# 4_SD_Card_NFC.net
KiCad netlist of a schematic drawn in Altium Designer
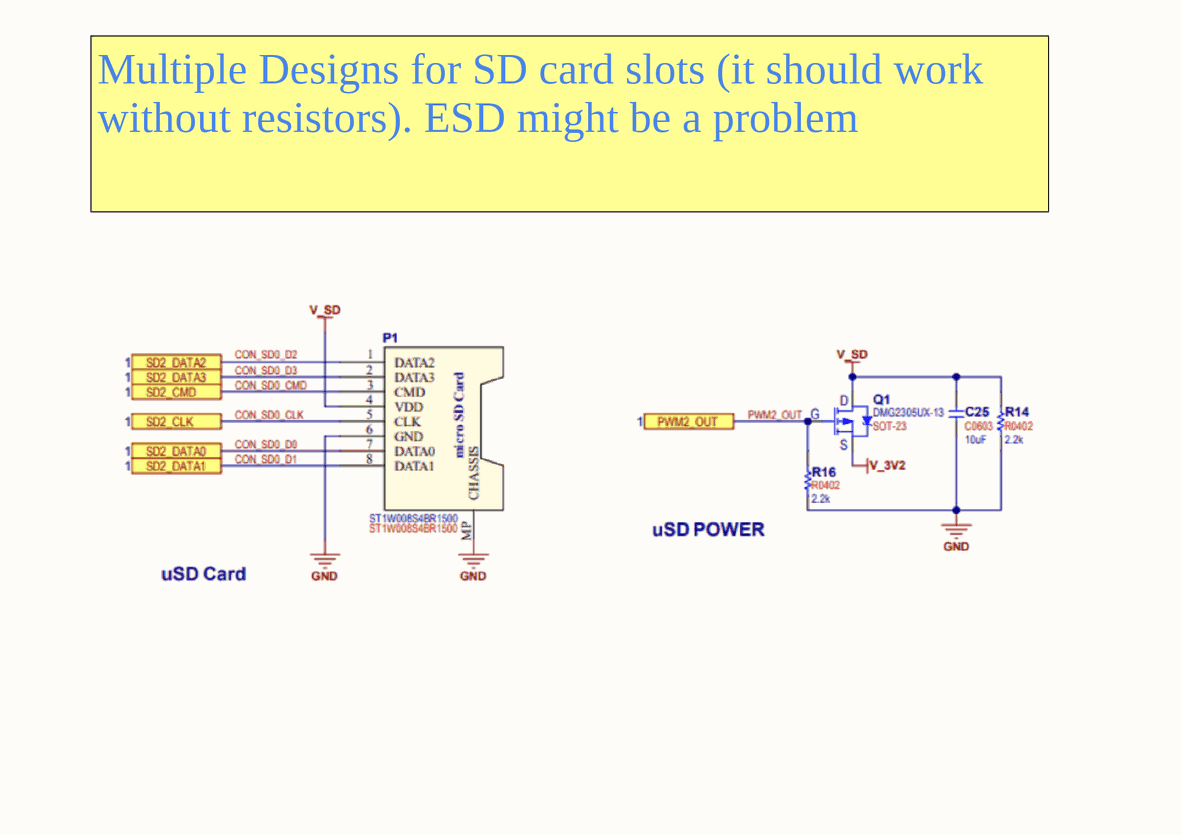
[diagram p0: 4_SD_Card_NFC.SchDoc, top middle]
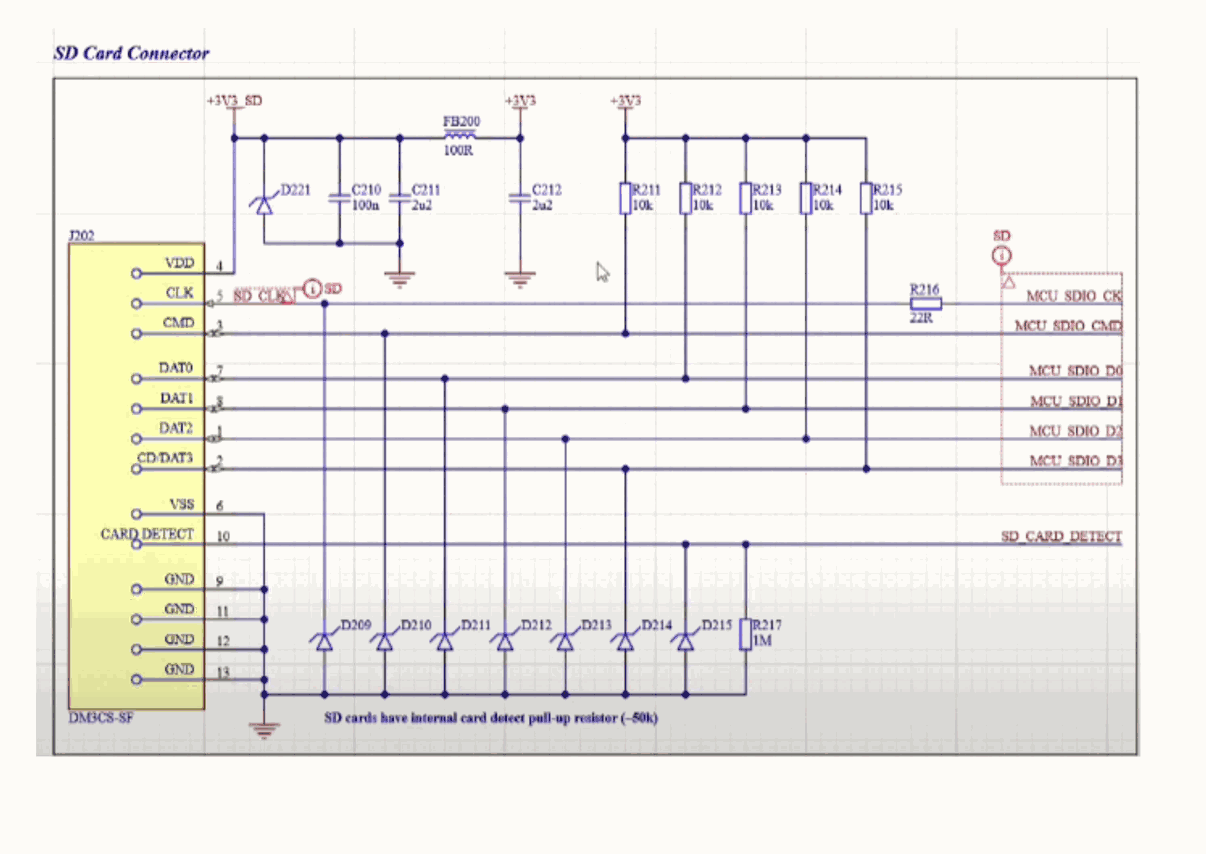
[diagram p1: 4_SD_Card_NFC.SchDoc, bottom left]
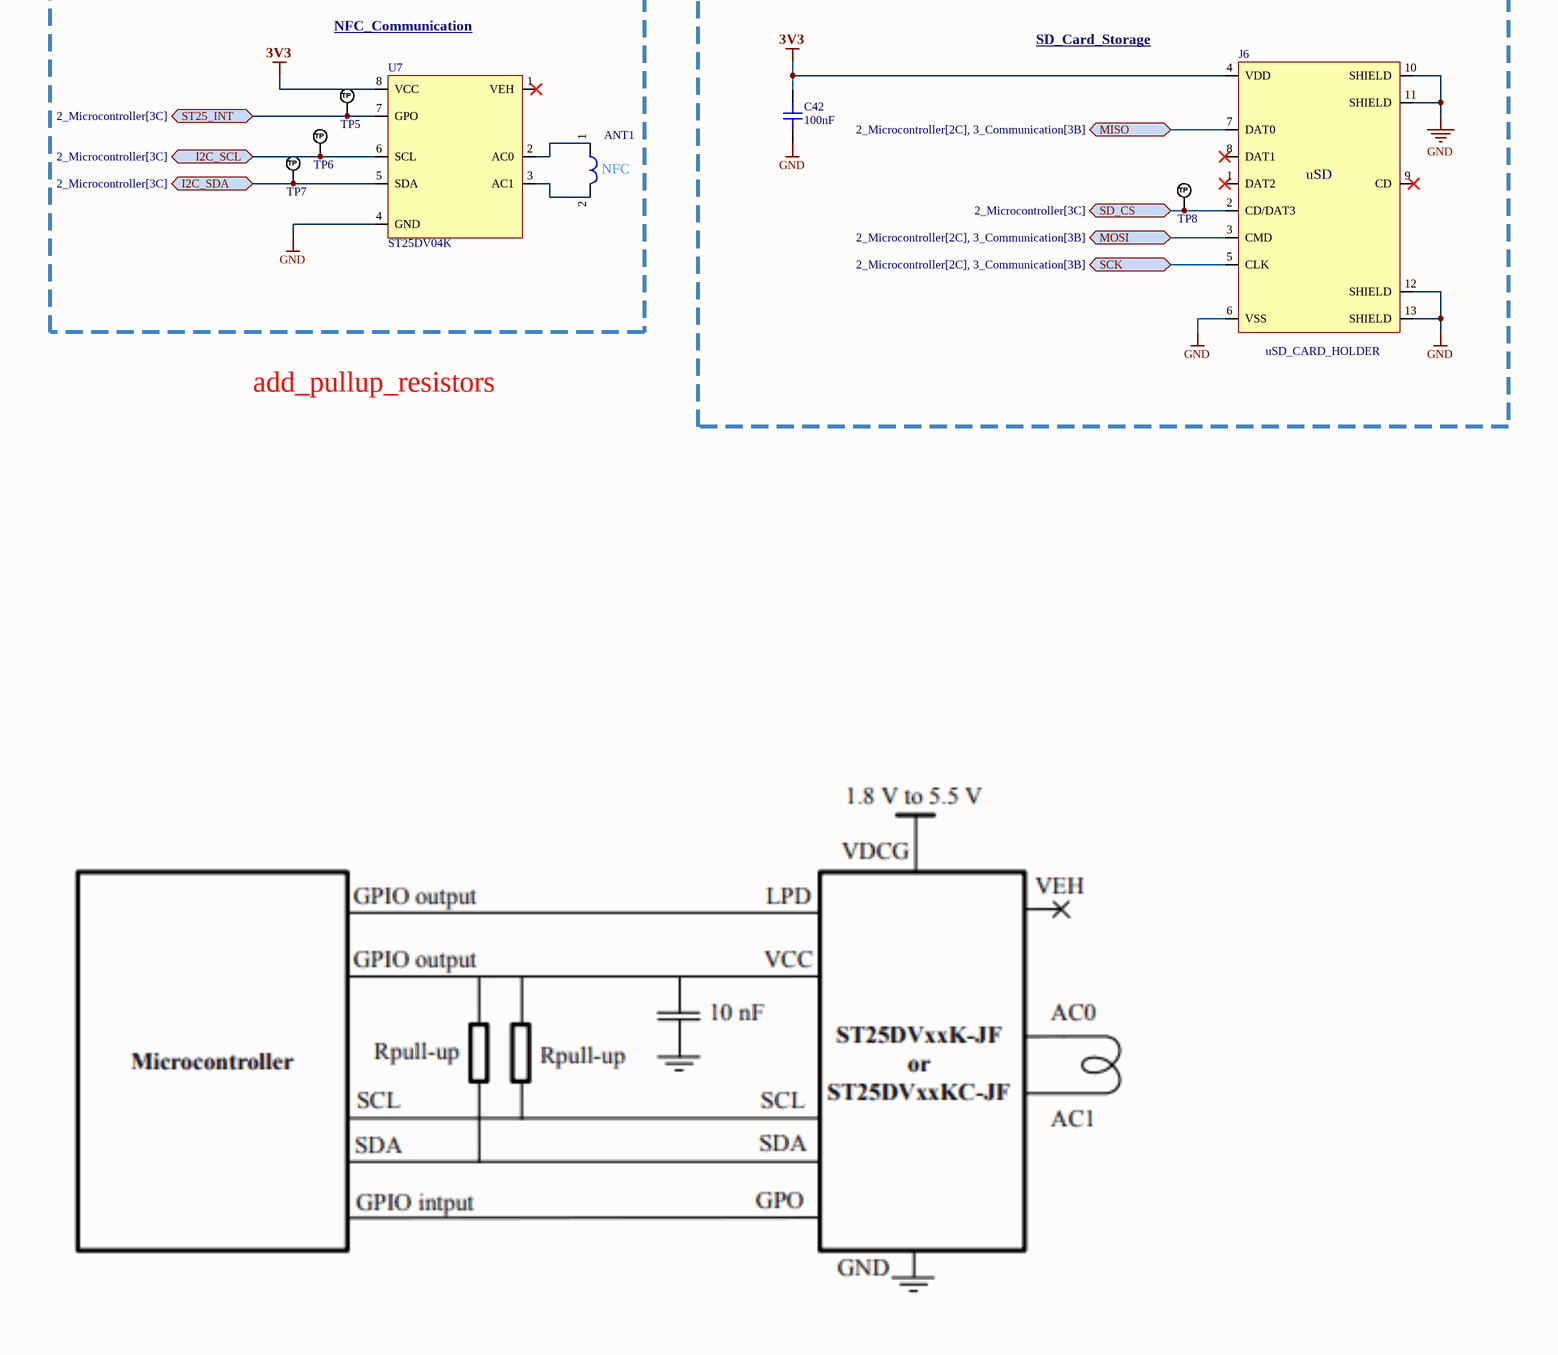
[diagram p2: 4_SD_Card_NFC.SchDoc, bottom middle]
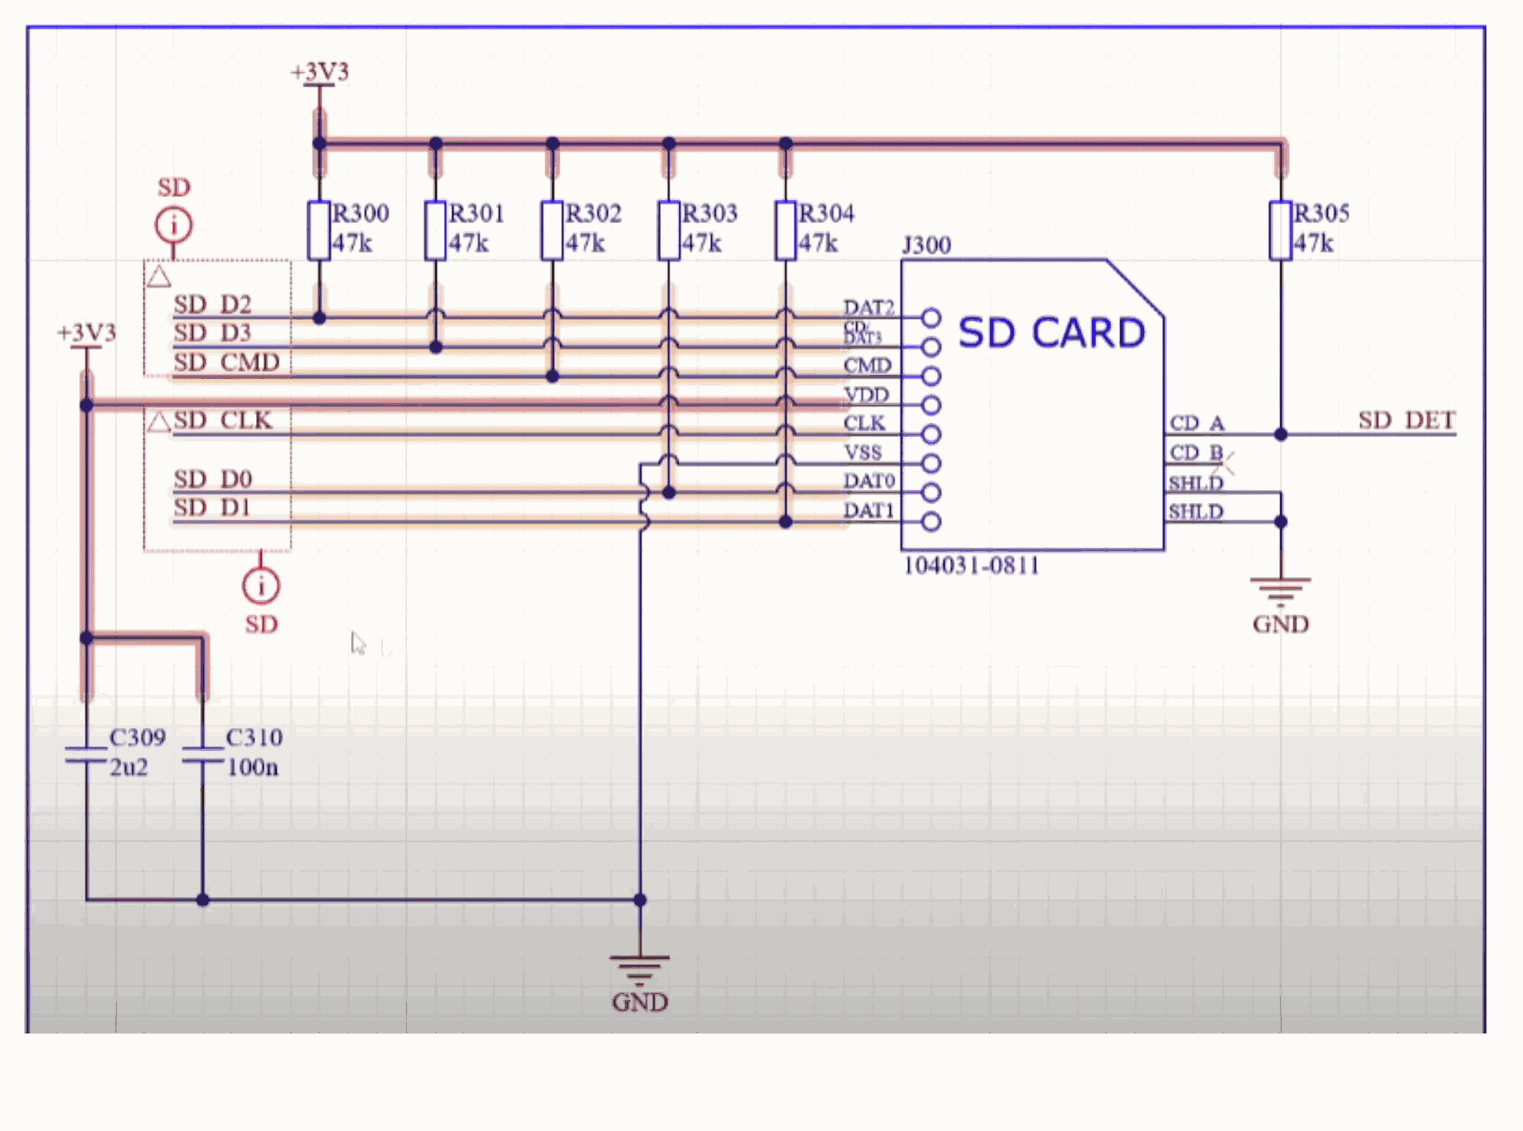
[diagram p3: 4_SD_Card_NFC.SchDoc, bottom right]

(export (version "E")
  (design (tool "Eeschema 10.0.6"))
  (components
    (comp (ref "ANT1") (value "NFC_ANTENNA") (libsource (lib "Schlib1") (part "NFC_ANTENNA")))
    (comp (ref "C42")
      (value "100nF")
      (footprint "CAP_0603")
      (description "Capacitor SMD 0603")
      (libsource (lib "Schlib_H2") (part "CAP_0603"))
    )
    (comp (ref "J6") (value "uSD_CARD_HOLDER") (libsource (lib "Schlib_H2") (part "uSD_CARD")))
    (comp (ref "TP5")
      (value "TP_NOBOM")
      (footprint "PAD_RND_1MM")
      (description "Test Point Round 1mm (NO BOM)")
      (libsource (lib "Schlib_H2") (part "TEST_POINT_RND_1MM"))
    )
    (comp (ref "TP6")
      (value "TP_NOBOM")
      (footprint "PAD_RND_1MM")
      (description "Test Point Round 1mm (NO BOM)")
      (libsource (lib "Schlib_H2") (part "TEST_POINT_RND_1MM"))
    )
    (comp (ref "TP7")
      (value "TP_NOBOM")
      (footprint "PAD_RND_1MM")
      (description "Test Point Round 1mm (NO BOM)")
      (libsource (lib "Schlib_H2") (part "TEST_POINT_RND_1MM"))
    )
    (comp (ref "TP8")
      (value "TP_NOBOM")
      (footprint "PAD_RND_1MM")
      (description "Test Point Round 1mm (NO BOM)")
      (libsource (lib "Schlib_H2") (part "TEST_POINT_RND_1MM"))
    )
    (comp (ref "U7")
      (value "ST25DV04K")
      (description "ST25DO4K NFC module with I2C")
      (libsource (lib "Schlib1") (part "ST25DV04K"))
    )
  )
  (nets
    (net (code "1") (name "/I2C_SCL") (class "Default")
      (node (ref "TP6") (pin "1") (pinfunction "TP_1") (pintype "passive"))
      (node (ref "U7") (pin "6") (pinfunction "SCL_6") (pintype "passive"))
    )
    (net (code "2") (name "/I2C_SDA") (class "Default")
      (node (ref "TP7") (pin "1") (pinfunction "TP_1") (pintype "passive"))
      (node (ref "U7") (pin "5") (pinfunction "SDA_5") (pintype "passive"))
    )
    (net (code "3") (name "/MISO") (class "Default")
      (node (ref "J6") (pin "7") (pinfunction "DAT0_7") (pintype "passive"))
    )
    (net (code "4") (name "/MOSI") (class "Default")
      (node (ref "J6") (pin "3") (pinfunction "CMD_3") (pintype "passive"))
    )
    (net (code "5") (name "/SCK") (class "Default")
      (node (ref "J6") (pin "5") (pinfunction "CLK_5") (pintype "passive"))
    )
    (net (code "6") (name "/SD_CS") (class "Default")
      (node (ref "J6") (pin "2") (pinfunction "CD/DAT3_2") (pintype "passive"))
      (node (ref "TP8") (pin "1") (pinfunction "TP_1") (pintype "passive"))
    )
    (net (code "7") (name "/ST25_INT") (class "Default")
      (node (ref "TP5") (pin "1") (pinfunction "TP_1") (pintype "passive"))
      (node (ref "U7") (pin "7") (pinfunction "GPO_7") (pintype "passive"))
    )
    (net (code "8") (name "3V3") (class "Default")
      (node (ref "C42") (pin "2") (pinfunction "2_2") (pintype "passive"))
      (node (ref "J6") (pin "4") (pinfunction "VDD_4") (pintype "passive"))
      (node (ref "U7") (pin "8") (pinfunction "VCC_8") (pintype "passive"))
    )
    (net (code "9") (name "GND") (class "Default")
      (node (ref "C42") (pin "1") (pinfunction "1_1") (pintype "passive"))
      (node (ref "J6") (pin "10") (pinfunction "SHIELD_10") (pintype "passive"))
      (node (ref "J6") (pin "11") (pinfunction "SHIELD_11") (pintype "passive"))
      (node (ref "J6") (pin "12") (pinfunction "SHIELD_12") (pintype "passive"))
      (node (ref "J6") (pin "13") (pinfunction "SHIELD_13") (pintype "passive"))
      (node (ref "J6") (pin "6") (pinfunction "VSS_6") (pintype "passive"))
      (node (ref "U7") (pin "4") (pinfunction "GND_4") (pintype "passive"))
    )
    (net (code "10") (name "Net-(U7-AC0)") (class "Default")
      (node (ref "ANT1") (pin "1") (pinfunction "1_1") (pintype "passive"))
      (node (ref "U7") (pin "2") (pinfunction "AC0_2") (pintype "passive"))
    )
    (net (code "11") (name "Net-(U7-AC1)") (class "Default")
      (node (ref "ANT1") (pin "2") (pinfunction "2_2") (pintype "passive"))
      (node (ref "U7") (pin "3") (pinfunction "AC1_3") (pintype "passive"))
    )
    (net (code "12") (name "unconnected-(J6-CD-Pad9)") (class "Default")
      (node (ref "J6") (pin "9") (pinfunction "CD_9") (pintype "passive+no_connect"))
    )
    (net (code "13") (name "unconnected-(J6-DAT1-Pad8)") (class "Default")
      (node (ref "J6") (pin "8") (pinfunction "DAT1_8") (pintype "passive+no_connect"))
    )
    (net (code "14") (name "unconnected-(J6-DAT2-Pad1)") (class "Default")
      (node (ref "J6") (pin "1") (pinfunction "DAT2_1") (pintype "passive+no_connect"))
    )
    (net (code "15") (name "unconnected-(U7-VEH-Pad1)") (class "Default")
      (node (ref "U7") (pin "1") (pinfunction "VEH_1") (pintype "passive+no_connect"))
    )
  )
)
